# musIR-tiny-mk-1_0.net
KiCad netlist of a schematic drawn in EAGLE
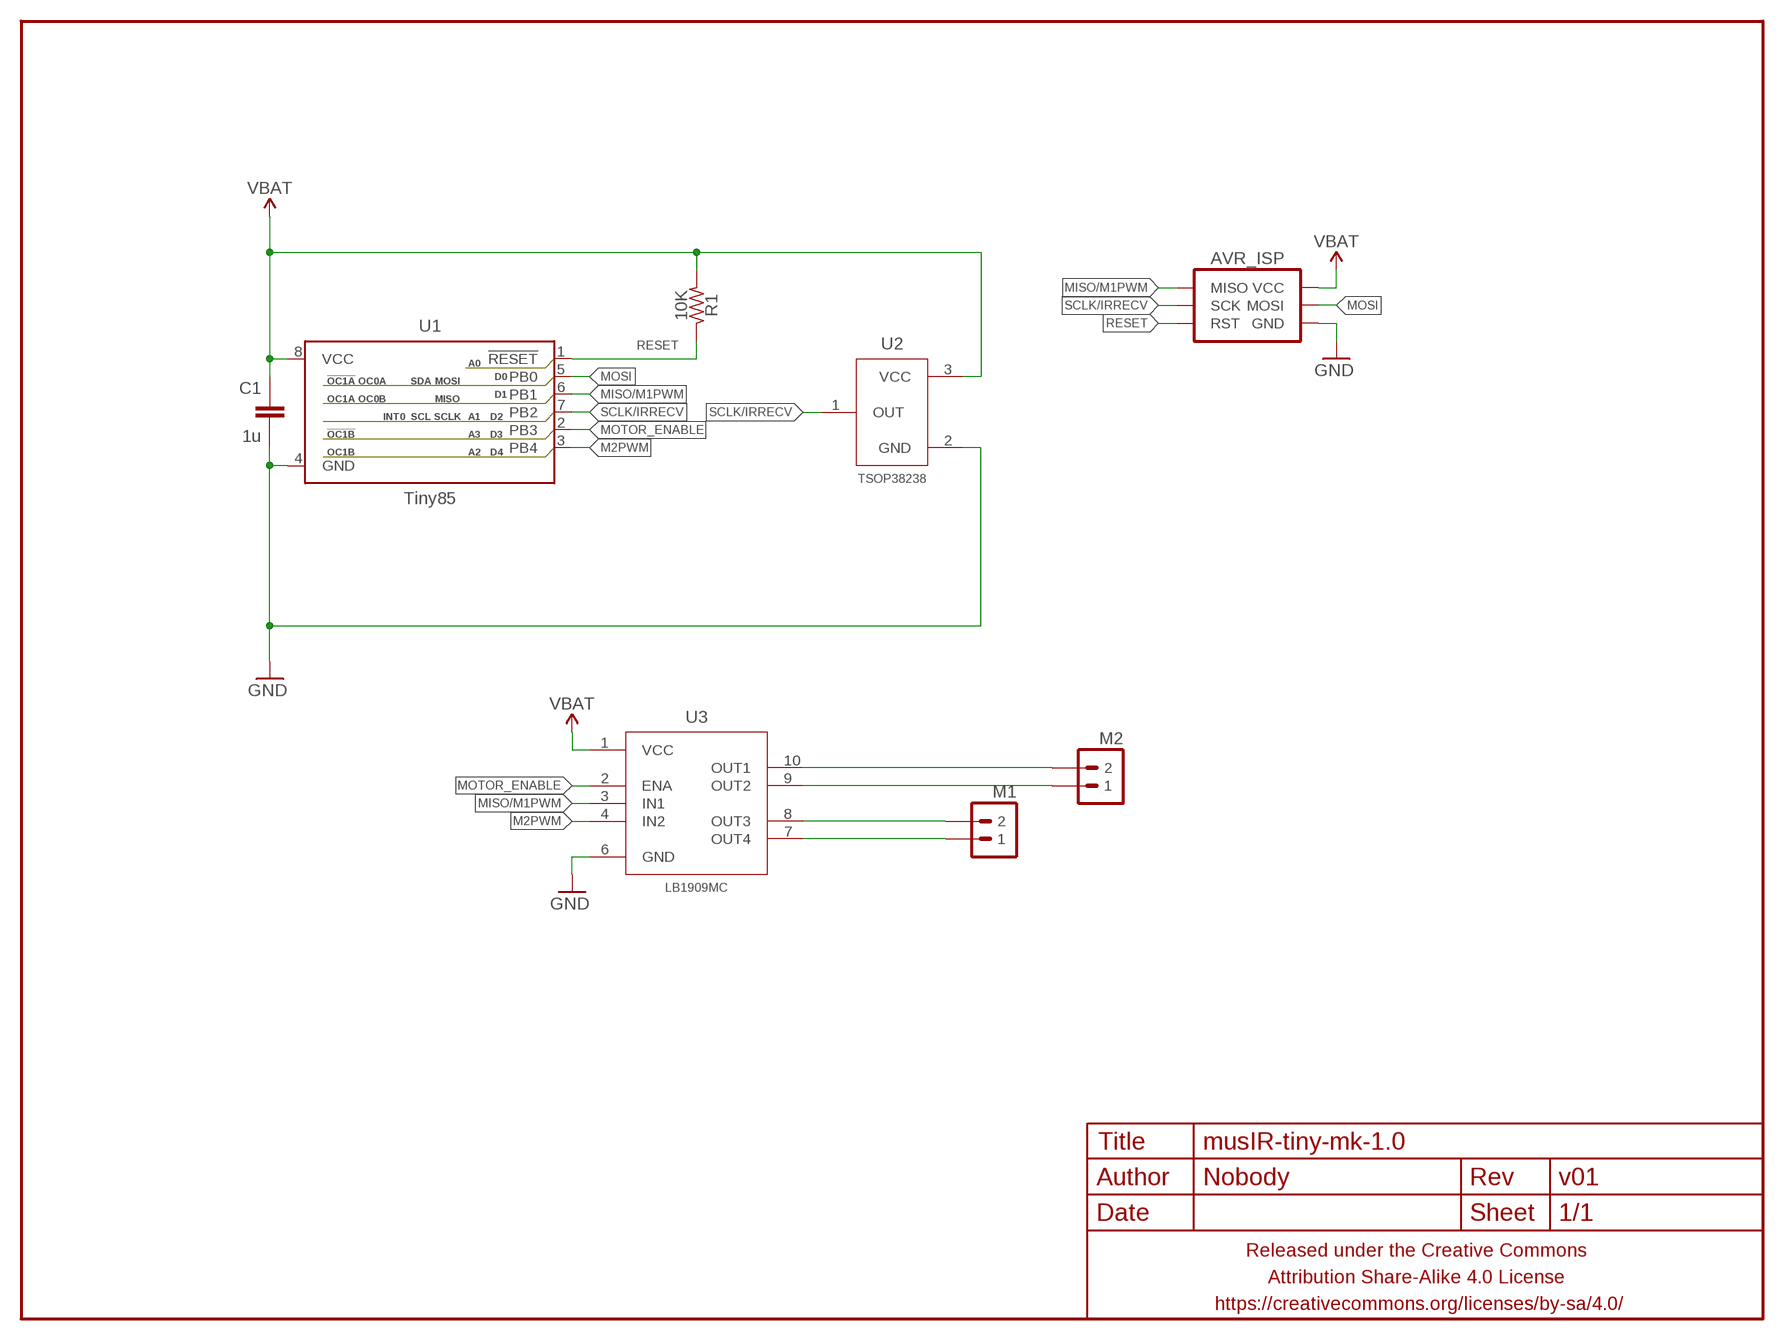
[diagram p0: schematic, sheet 1]

(export (version "E")
  (design (tool "Eeschema 10.0.6"))
  (components
    (comp (ref "AVR_ISP")
      (value "AVR_SPI_PRG_6TESTPOINTS")
      (footprint "eagle-import:2X3_TEST_POINTS")
      (libsource (lib "eagle-import") (part "AVR_SPI_PRG_6TESTPOINTS"))
    )
    (comp (ref "C1")
      (value "1u")
      (footprint "eagle-import:C0603-TIGHTER")
      (libsource (lib "eagle-import") (part "CAPACITOR-CERAMICC0603-TIGHTER"))
    )
    (comp (ref "FRAME1")
      (value "FRAME-LETTERNO_PACKAGE")
      (footprint "eagle-import:DUMMY")
      (fields (field (name "DESIGNER") "Nobody"))
      (libsource (lib "eagle-import") (part "FRAME-LETTERNO_PACKAGE"))
    )
    (comp (ref "M1")
      (value "M02PTH-CENTERED")
      (footprint "eagle-import:1X02-CENTER")
      (libsource (lib "eagle-import") (part "M02PTH-CENTERED"))
    )
    (comp (ref "M2")
      (value "M02PTH-CENTERED")
      (footprint "eagle-import:1X02-CENTER")
      (libsource (lib "eagle-import") (part "M02PTH-CENTERED"))
    )
    (comp (ref "R1")
      (value "10K")
      (footprint "eagle-import:R0603-TIGHTER")
      (libsource (lib "eagle-import") (part "RESISTORR0603-TIGHTER"))
    )
    (comp (ref "U1")
      (value "Tiny85")
      (footprint "eagle-import:SO08-EIAJ")
      (libsource (lib "eagle-import") (part "ATTINY45TINY85-20-SOICW"))
    )
    (comp (ref "U2")
      (value "TSOP38238")
      (footprint "eagle-import:TSOP38238")
      (libsource (lib "eagle-import") (part "TSOP382__/4__"))
    )
    (comp (ref "U3")
      (value "LB1909MC")
      (footprint "eagle-import:SO10-NOTREALLY")
      (libsource (lib "eagle-import") (part "LB1909MC"))
    )
  )
  (nets
    (net (code "1") (name "GND") (class "Default")
      (node (ref "AVR_ISP") (pin "6") (pinfunction "GND_6") (pintype "passive"))
      (node (ref "C1") (pin "2") (pinfunction "2_2") (pintype "passive"))
      (node (ref "U1") (pin "4") (pinfunction "GND_4") (pintype "bidirectional"))
      (node (ref "U2") (pin "2") (pinfunction "GND_2") (pintype "bidirectional"))
      (node (ref "U3") (pin "6") (pinfunction "GND_6") (pintype "bidirectional"))
    )
    (net (code "2") (name "M2PWM") (class "Default")
      (node (ref "U1") (pin "3") (pinfunction "PB4_3") (pintype "bidirectional"))
      (node (ref "U3") (pin "4") (pinfunction "IN2_4") (pintype "bidirectional"))
    )
    (net (code "3") (name "MISO{slash}M1PWM") (class "Default")
      (node (ref "AVR_ISP") (pin "1") (pinfunction "MISO_1") (pintype "passive"))
      (node (ref "U1") (pin "6") (pinfunction "PB1_6") (pintype "bidirectional"))
      (node (ref "U3") (pin "3") (pinfunction "IN1_3") (pintype "bidirectional"))
    )
    (net (code "4") (name "MOSI") (class "Default")
      (node (ref "AVR_ISP") (pin "4") (pinfunction "MOSI_4") (pintype "passive"))
      (node (ref "U1") (pin "5") (pinfunction "PB0_5") (pintype "bidirectional"))
    )
    (net (code "5") (name "MOTOR_ENABLE") (class "Default")
      (node (ref "U1") (pin "2") (pinfunction "PB3_2") (pintype "bidirectional"))
      (node (ref "U3") (pin "2") (pinfunction "ENA_2") (pintype "bidirectional"))
    )
    (net (code "6") (name "Net-(U3-OUT1)") (class "Default")
      (node (ref "M2") (pin "2") (pinfunction "2_2") (pintype "passive"))
      (node (ref "U3") (pin "10") (pinfunction "OUT1_10") (pintype "bidirectional"))
    )
    (net (code "7") (name "Net-(U3-OUT2)") (class "Default")
      (node (ref "M2") (pin "1") (pinfunction "1_1") (pintype "passive"))
      (node (ref "U3") (pin "9") (pinfunction "OUT2_9") (pintype "bidirectional"))
    )
    (net (code "8") (name "Net-(U3-OUT3)") (class "Default")
      (node (ref "M1") (pin "2") (pinfunction "2_2") (pintype "passive"))
      (node (ref "U3") (pin "8") (pinfunction "OUT3_8") (pintype "bidirectional"))
    )
    (net (code "9") (name "Net-(U3-OUT4)") (class "Default")
      (node (ref "M1") (pin "1") (pinfunction "1_1") (pintype "passive"))
      (node (ref "U3") (pin "7") (pinfunction "OUT4_7") (pintype "bidirectional"))
    )
    (net (code "10") (name "RESET") (class "Default")
      (node (ref "AVR_ISP") (pin "5") (pinfunction "RST_5") (pintype "passive"))
      (node (ref "R1") (pin "1") (pinfunction "1_1") (pintype "passive"))
      (node (ref "U1") (pin "1") (pinfunction "~{RESET}_1") (pintype "bidirectional"))
    )
    (net (code "11") (name "SCLK{slash}IRRECV") (class "Default")
      (node (ref "AVR_ISP") (pin "3") (pinfunction "SCK_3") (pintype "passive"))
      (node (ref "U1") (pin "7") (pinfunction "PB2_7") (pintype "bidirectional"))
      (node (ref "U2") (pin "1") (pinfunction "OUT_1") (pintype "bidirectional"))
    )
    (net (code "12") (name "VBAT") (class "Default")
      (node (ref "AVR_ISP") (pin "2") (pinfunction "VCC_2") (pintype "passive"))
      (node (ref "C1") (pin "1") (pinfunction "1_1") (pintype "passive"))
      (node (ref "R1") (pin "2") (pinfunction "2_2") (pintype "passive"))
      (node (ref "U1") (pin "8") (pinfunction "VCC_8") (pintype "bidirectional"))
      (node (ref "U2") (pin "3") (pinfunction "VCC_3") (pintype "bidirectional"))
      (node (ref "U3") (pin "1") (pinfunction "VCC_1") (pintype "bidirectional"))
    )
  )
)
